# bbf-dc-outputs.net
KiCad netlist of a schematic drawn in EAGLE
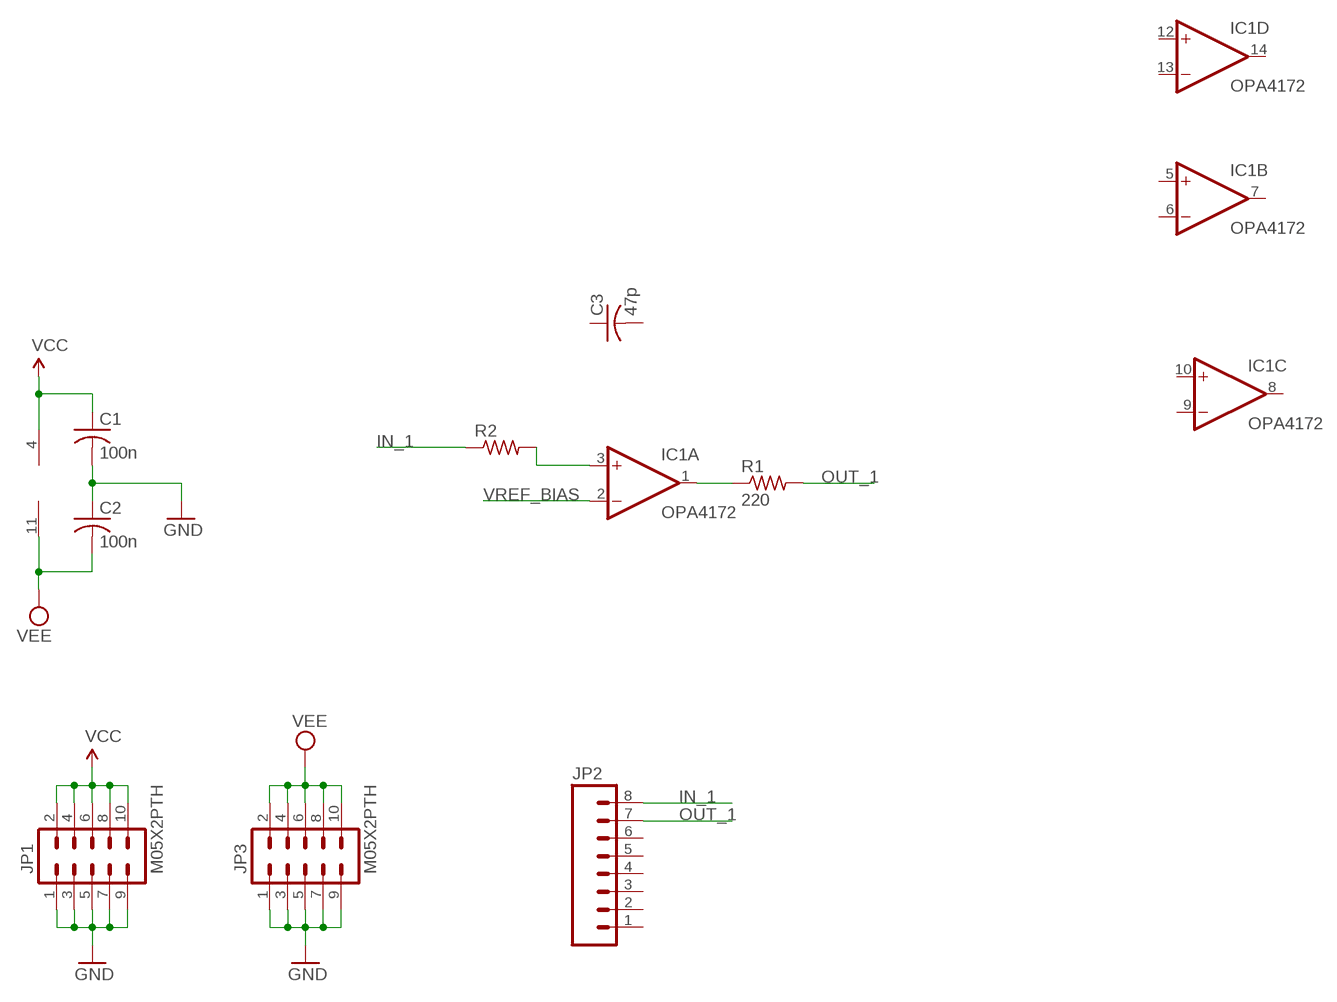
[diagram p0: schematic, sheet 1]

(export (version "E")
  (design (tool "Eeschema 10.0.6"))
  (components
    (comp (ref "C1")
      (value "100n")
      (footprint "eagle-import:C0805")
      (libsource (lib "eagle-import") (part "C-USC0805"))
    )
    (comp (ref "C2")
      (value "100n")
      (footprint "eagle-import:C0805")
      (libsource (lib "eagle-import") (part "C-USC0805"))
    )
    (comp (ref "C3")
      (value "47p")
      (footprint "eagle-import:C0805")
      (libsource (lib "eagle-import") (part "C-USC0805"))
    )
    (comp (ref "IC1")
      (value "OPA4172")
      (footprint "eagle-import:SO14")
      (libsource (lib "eagle-import") (part "OPA4172IDR_SO14"))
    )
    (comp (ref "JP1")
      (value "M05X2PTH")
      (footprint "eagle-import:AVR_ICSP")
      (libsource (lib "eagle-import") (part "M05X2PTH"))
    )
    (comp (ref "JP2")
      (value "M08")
      (footprint "eagle-import:1X08")
      (libsource (lib "eagle-import") (part "M08"))
    )
    (comp (ref "JP3")
      (value "M05X2PTH")
      (footprint "eagle-import:AVR_ICSP")
      (libsource (lib "eagle-import") (part "M05X2PTH"))
    )
    (comp (ref "R1")
      (value "220")
      (footprint "eagle-import:R0805")
      (libsource (lib "eagle-import") (part "R-US_R0805"))
    )
    (comp (ref "R2")
      (value "R-US_R0805")
      (footprint "eagle-import:R0805")
      (libsource (lib "eagle-import") (part "R-US_R0805"))
    )
  )
  (nets
    (net (code "1") (name "/IN_1") (class "Default")
      (node (ref "JP2") (pin "8") (pinfunction "8_8") (pintype "passive"))
      (node (ref "R2") (pin "1") (pinfunction "1_1") (pintype "passive"))
    )
    (net (code "2") (name "/OUT_1") (class "Default")
      (node (ref "JP2") (pin "7") (pinfunction "7_7") (pintype "passive"))
      (node (ref "R1") (pin "2") (pinfunction "2_2") (pintype "passive"))
    )
    (net (code "3") (name "/VREF_BIAS") (class "Default")
      (node (ref "IC1") (pin "2") (pinfunction "-IN_2") (pintype "input"))
    )
    (net (code "4") (name "GND") (class "Default")
      (node (ref "C1") (pin "2") (pinfunction "2_2") (pintype "passive"))
      (node (ref "C2") (pin "1") (pinfunction "1_1") (pintype "passive"))
      (node (ref "JP1") (pin "1") (pinfunction "1_1") (pintype "passive"))
      (node (ref "JP1") (pin "3") (pinfunction "3_3") (pintype "passive"))
      (node (ref "JP1") (pin "5") (pinfunction "5_5") (pintype "passive"))
      (node (ref "JP1") (pin "7") (pinfunction "7_7") (pintype "passive"))
      (node (ref "JP1") (pin "9") (pinfunction "9_9") (pintype "passive"))
      (node (ref "JP3") (pin "1") (pinfunction "1_1") (pintype "passive"))
      (node (ref "JP3") (pin "3") (pinfunction "3_3") (pintype "passive"))
      (node (ref "JP3") (pin "5") (pinfunction "5_5") (pintype "passive"))
      (node (ref "JP3") (pin "7") (pinfunction "7_7") (pintype "passive"))
      (node (ref "JP3") (pin "9") (pinfunction "9_9") (pintype "passive"))
    )
    (net (code "5") (name "Net-(IC1A-+IN)") (class "Default")
      (node (ref "IC1") (pin "3") (pinfunction "+IN_3") (pintype "input"))
      (node (ref "R2") (pin "2") (pinfunction "2_2") (pintype "passive"))
    )
    (net (code "6") (name "Net-(IC1A-OUT)") (class "Default")
      (node (ref "IC1") (pin "1") (pinfunction "OUT_1") (pintype "output"))
      (node (ref "R1") (pin "1") (pinfunction "1_1") (pintype "passive"))
    )
    (net (code "7") (name "VCC") (class "Default")
      (node (ref "C1") (pin "1") (pinfunction "1_1") (pintype "passive"))
      (node (ref "IC1") (pin "4") (pinfunction "V+_4") (pintype "power_in"))
      (node (ref "JP1") (pin "10") (pinfunction "10_10") (pintype "passive"))
      (node (ref "JP1") (pin "2") (pinfunction "2_2") (pintype "passive"))
      (node (ref "JP1") (pin "4") (pinfunction "4_4") (pintype "passive"))
      (node (ref "JP1") (pin "6") (pinfunction "6_6") (pintype "passive"))
      (node (ref "JP1") (pin "8") (pinfunction "8_8") (pintype "passive"))
    )
    (net (code "8") (name "VEE") (class "Default")
      (node (ref "C2") (pin "2") (pinfunction "2_2") (pintype "passive"))
      (node (ref "IC1") (pin "11") (pinfunction "V-_11") (pintype "power_in"))
      (node (ref "JP3") (pin "10") (pinfunction "10_10") (pintype "passive"))
      (node (ref "JP3") (pin "2") (pinfunction "2_2") (pintype "passive"))
      (node (ref "JP3") (pin "4") (pinfunction "4_4") (pintype "passive"))
      (node (ref "JP3") (pin "6") (pinfunction "6_6") (pintype "passive"))
      (node (ref "JP3") (pin "8") (pinfunction "8_8") (pintype "passive"))
    )
    (net (code "9") (name "unconnected-(C3-Pad1)") (class "Default")
      (node (ref "C3") (pin "1") (pinfunction "1_1") (pintype "passive"))
    )
    (net (code "10") (name "unconnected-(C3-Pad2)") (class "Default")
      (node (ref "C3") (pin "2") (pinfunction "2_2") (pintype "passive"))
    )
    (net (code "11") (name "unconnected-(IC1B-+IN-Pad5)") (class "Default")
      (node (ref "IC1") (pin "5") (pinfunction "+IN_5") (pintype "input"))
    )
    (net (code "12") (name "unconnected-(IC1B--IN-Pad6)") (class "Default")
      (node (ref "IC1") (pin "6") (pinfunction "-IN_6") (pintype "input"))
    )
    (net (code "13") (name "unconnected-(IC1B-OUT-Pad7)") (class "Default")
      (node (ref "IC1") (pin "7") (pinfunction "OUT_7") (pintype "output"))
    )
    (net (code "14") (name "unconnected-(IC1C-+IN-Pad10)") (class "Default")
      (node (ref "IC1") (pin "10") (pinfunction "+IN_10") (pintype "input"))
    )
    (net (code "15") (name "unconnected-(IC1C--IN-Pad9)") (class "Default")
      (node (ref "IC1") (pin "9") (pinfunction "-IN_9") (pintype "input"))
    )
    (net (code "16") (name "unconnected-(IC1C-OUT-Pad8)") (class "Default")
      (node (ref "IC1") (pin "8") (pinfunction "OUT_8") (pintype "output"))
    )
    (net (code "17") (name "unconnected-(IC1D-+IN-Pad12)") (class "Default")
      (node (ref "IC1") (pin "12") (pinfunction "+IN_12") (pintype "input"))
    )
    (net (code "18") (name "unconnected-(IC1D--IN-Pad13)") (class "Default")
      (node (ref "IC1") (pin "13") (pinfunction "-IN_13") (pintype "input"))
    )
    (net (code "19") (name "unconnected-(IC1D-OUT-Pad14)") (class "Default")
      (node (ref "IC1") (pin "14") (pinfunction "OUT_14") (pintype "output"))
    )
    (net (code "20") (name "unconnected-(JP2-Pad1)") (class "Default")
      (node (ref "JP2") (pin "1") (pinfunction "1_1") (pintype "passive"))
    )
    (net (code "21") (name "unconnected-(JP2-Pad2)") (class "Default")
      (node (ref "JP2") (pin "2") (pinfunction "2_2") (pintype "passive"))
    )
    (net (code "22") (name "unconnected-(JP2-Pad3)") (class "Default")
      (node (ref "JP2") (pin "3") (pinfunction "3_3") (pintype "passive"))
    )
    (net (code "23") (name "unconnected-(JP2-Pad4)") (class "Default")
      (node (ref "JP2") (pin "4") (pinfunction "4_4") (pintype "passive"))
    )
    (net (code "24") (name "unconnected-(JP2-Pad5)") (class "Default")
      (node (ref "JP2") (pin "5") (pinfunction "5_5") (pintype "passive"))
    )
    (net (code "25") (name "unconnected-(JP2-Pad6)") (class "Default")
      (node (ref "JP2") (pin "6") (pinfunction "6_6") (pintype "passive"))
    )
  )
)
